# Sheet1.net
KiCad netlist of a schematic drawn in Altium Designer
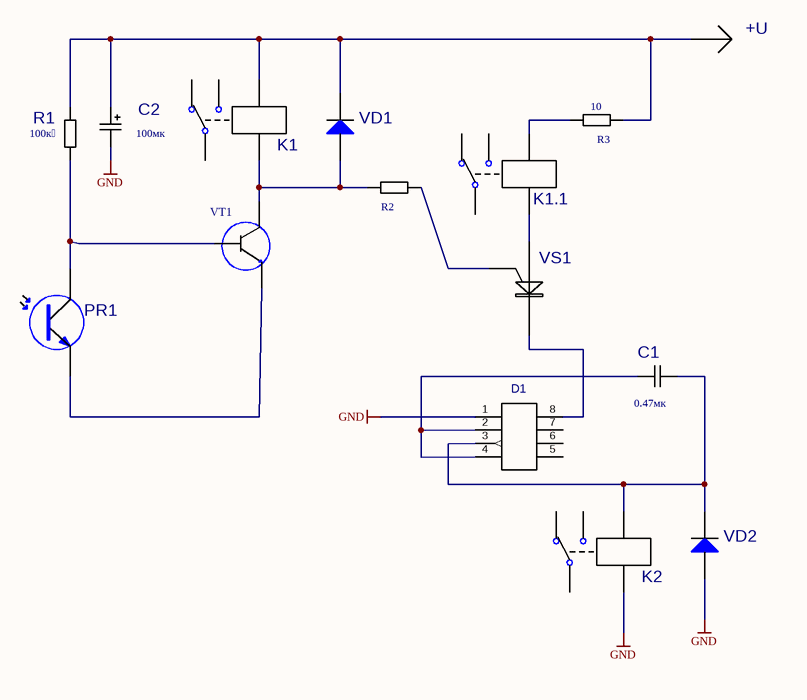
[diagram p0: Sheet1.SCHDOC]

(export (version "E")
  (design (tool "Eeschema 10.0.6"))
  (components
    (comp (ref "+U")
      (value "PLUG")
      (footprint "PIN1")
      (fields (field (name "PUBLISHER") "Altium Limited"))
      (libsource (lib "*") (part "PLUG"))
    )
    (comp (ref "C1")
      (value "0.47мк")
      (footprint "RAD-0.3")
      (description "CAP")
      (fields (field (name "PUBLISHER") "Altium Limited"))
      (libsource (lib "*") (part "CAP"))
    )
    (comp (ref "C2")
      (value "100мк")
      (footprint "RB7.6-15")
      (description "CAP_POL1")
      (fields (field (name "PUBLISHER") "Altium Limited"))
      (libsource (lib "*") (part "CAP_POL1"))
    )
    (comp (ref "D1") (value "KP1006ВИ1") (footprint "KP1006ВИ1") (libsource (lib "*") (part "KP1006ВИ1")))
    (comp (ref "K1")
      (value "RELAY-SPDT")
      (footprint "DIP-P5/X1.65")
      (fields (field (name "PUBLISHER") "Altium Limited"))
      (libsource (lib "*") (part "RELAY-SPDT"))
    )
    (comp (ref "K1.1")
      (value "RELAY-SPDT")
      (footprint "DIP-P5/X1.65")
      (fields (field (name "PUBLISHER") "Altium Limited"))
      (libsource (lib "*") (part "RELAY-SPDT"))
    )
    (comp (ref "K2")
      (value "RELAY-SPDT")
      (footprint "DIP-P5/X1.65")
      (fields (field (name "PUBLISHER") "Altium Limited"))
      (libsource (lib "") (part "RELAY-SPDT_1"))
    )
    (comp (ref "PR1")
      (value "PHOTO_NPN")
      (footprint "SFM-T2(3)/X1.6V")
      (fields (field (name "PUBLISHER") "Altium Limited"))
      (libsource (lib "*") (part "PHOTO_NPN"))
    )
    (comp (ref "R1")
      (value "100к")
      (footprint "AXIAL-0.4")
      (description "RES2")
      (fields (field (name "PUBLISHER") "Altium Limited"))
      (libsource (lib "*") (part "RES2"))
    )
    (comp (ref "R2")
      (value "RES2")
      (footprint "AXIAL-0.4")
      (fields (field (name "PUBLISHER") "Altium Limited"))
      (libsource (lib "*") (part "RES2"))
    )
    (comp (ref "R3")
      (value "10")
      (footprint "AXIAL-0.4")
      (description "RES2")
      (fields (field (name "PUBLISHER") "Altium Limited"))
      (libsource (lib "*") (part "RES2"))
    )
    (comp (ref "VD1")
      (value "DIODE_1N914")
      (footprint "DIO7.1-3.9X1.9")
      (fields (field (name "PUBLISHER") "Altium Limited"))
      (libsource (lib "*") (part "DIODE_1N914"))
    )
    (comp (ref "VD2")
      (value "DIODE_1N914")
      (footprint "DIO7.1-3.9X1.9")
      (fields (field (name "PUBLISHER") "Altium Limited"))
      (libsource (lib "*") (part "DIODE_1N914"))
    )
    (comp (ref "VS1")
      (value "PUT")
      (description "Programmable Unijunction Transistor")
      (libsource (lib "*") (part "PUT"))
    )
    (comp (ref "VT1") (value "КТ315") (footprint "КТ315") (libsource (lib "*") (part "КТ315")))
  )
  (nets
    (net (code "1") (name "GND") (class "Default")
      (node (ref "C2") (pin "2") (pinfunction "2_2") (pintype "passive"))
      (node (ref "D1") (pin "1") (pintype "passive"))
      (node (ref "K2") (pin "4") (pinfunction "4_4") (pintype "passive"))
      (node (ref "VD2") (pin "1") (pinfunction "A_1") (pintype "passive"))
    )
    (net (code "2") (name "Net-(C1-Pad1)") (class "Default")
      (node (ref "C1") (pin "1") (pinfunction "1_1") (pintype "passive"))
      (node (ref "D1") (pin "2") (pintype "passive"))
      (node (ref "D1") (pin "4") (pintype "passive"))
    )
    (net (code "3") (name "Net-(K1.1-Pad5)") (class "Default")
      (node (ref "K1.1") (pin "5") (pinfunction "5_5") (pintype "passive"))
      (node (ref "R3") (pin "1") (pinfunction "1_1") (pintype "passive"))
    )
    (net (code "4") (name "Net-(PR1-C)") (class "Default")
      (node (ref "PR1") (pin "1") (pinfunction "C_1") (pintype "passive"))
      (node (ref "R1") (pin "1") (pinfunction "1_1") (pintype "passive"))
      (node (ref "VT1") (pin "B") (pinfunction "B_B") (pintype "passive"))
    )
    (net (code "5") (name "Net-(PR1-E)") (class "Default")
      (node (ref "PR1") (pin "3") (pinfunction "E_3") (pintype "passive"))
      (node (ref "VT1") (pin "E") (pinfunction "E_E") (pintype "passive"))
    )
    (net (code "6") (name "Net-(VD1-A)") (class "Default")
      (node (ref "K1") (pin "4") (pinfunction "4_4") (pintype "passive"))
      (node (ref "R2") (pin "1") (pinfunction "1_1") (pintype "passive"))
      (node (ref "VD1") (pin "1") (pinfunction "A_1") (pintype "passive"))
      (node (ref "VT1") (pin "K") (pinfunction "K_K") (pintype "passive"))
    )
    (net (code "7") (name "Net-(VD1-K)") (class "Default")
      (node (ref "+U") (pin "1") (pinfunction "1_1") (pintype "passive"))
      (node (ref "C2") (pin "1") (pinfunction "1_1") (pintype "passive"))
      (node (ref "K1") (pin "5") (pinfunction "5_5") (pintype "passive"))
      (node (ref "R1") (pin "2") (pinfunction "2_2") (pintype "passive"))
      (node (ref "R3") (pin "2") (pinfunction "2_2") (pintype "passive"))
      (node (ref "VD1") (pin "2") (pinfunction "K_2") (pintype "passive"))
    )
    (net (code "8") (name "Net-(VD2-K)") (class "Default")
      (node (ref "C1") (pin "2") (pinfunction "2_2") (pintype "passive"))
      (node (ref "D1") (pin "3") (pintype "output"))
      (node (ref "K2") (pin "5") (pinfunction "5_5") (pintype "passive"))
      (node (ref "VD2") (pin "2") (pinfunction "K_2") (pintype "passive"))
    )
    (net (code "9") (name "Net-(VS1-A)") (class "Default")
      (node (ref "K1.1") (pin "4") (pinfunction "4_4") (pintype "passive"))
      (node (ref "VS1") (pin "1") (pinfunction "A_1") (pintype "passive"))
    )
    (net (code "10") (name "Net-(VS1-G)") (class "Default")
      (node (ref "R2") (pin "2") (pinfunction "2_2") (pintype "passive"))
      (node (ref "VS1") (pin "2") (pinfunction "G_2") (pintype "passive"))
    )
    (net (code "11") (name "Net-(VS1-K)") (class "Default")
      (node (ref "D1") (pin "8") (pintype "passive"))
      (node (ref "VS1") (pin "3") (pinfunction "K_3") (pintype "passive"))
    )
    (net (code "12") (name "unconnected-(D1-Pad5)") (class "Default")
      (node (ref "D1") (pin "5") (pintype "passive"))
    )
    (net (code "13") (name "unconnected-(D1-Pad6)") (class "Default")
      (node (ref "D1") (pin "6") (pintype "passive"))
    )
    (net (code "14") (name "unconnected-(D1-Pad7)") (class "Default")
      (node (ref "D1") (pin "7") (pintype "passive"))
    )
    (net (code "15") (name "unconnected-(K1-Pad1)") (class "Default")
      (node (ref "K1") (pin "1") (pinfunction "1_1") (pintype "passive"))
    )
    (net (code "16") (name "unconnected-(K1-Pad2)") (class "Default")
      (node (ref "K1") (pin "2") (pinfunction "2_2") (pintype "passive"))
    )
    (net (code "17") (name "unconnected-(K1-Pad3)") (class "Default")
      (node (ref "K1") (pin "3") (pinfunction "3_3") (pintype "passive"))
    )
    (net (code "18") (name "unconnected-(K1.1-Pad1)") (class "Default")
      (node (ref "K1.1") (pin "1") (pinfunction "1_1") (pintype "passive"))
    )
    (net (code "19") (name "unconnected-(K1.1-Pad2)") (class "Default")
      (node (ref "K1.1") (pin "2") (pinfunction "2_2") (pintype "passive"))
    )
    (net (code "20") (name "unconnected-(K1.1-Pad3)") (class "Default")
      (node (ref "K1.1") (pin "3") (pinfunction "3_3") (pintype "passive"))
    )
    (net (code "21") (name "unconnected-(K2-Pad1)") (class "Default")
      (node (ref "K2") (pin "1") (pinfunction "1_1") (pintype "passive"))
    )
    (net (code "22") (name "unconnected-(K2-Pad2)") (class "Default")
      (node (ref "K2") (pin "2") (pinfunction "2_2") (pintype "passive"))
    )
    (net (code "23") (name "unconnected-(K2-Pad3)") (class "Default")
      (node (ref "K2") (pin "3") (pinfunction "3_3") (pintype "passive"))
    )
  )
)
